# BlinkBoard_micro_v1_JACDAC.net
KiCad netlist of a schematic drawn in Altium Designer
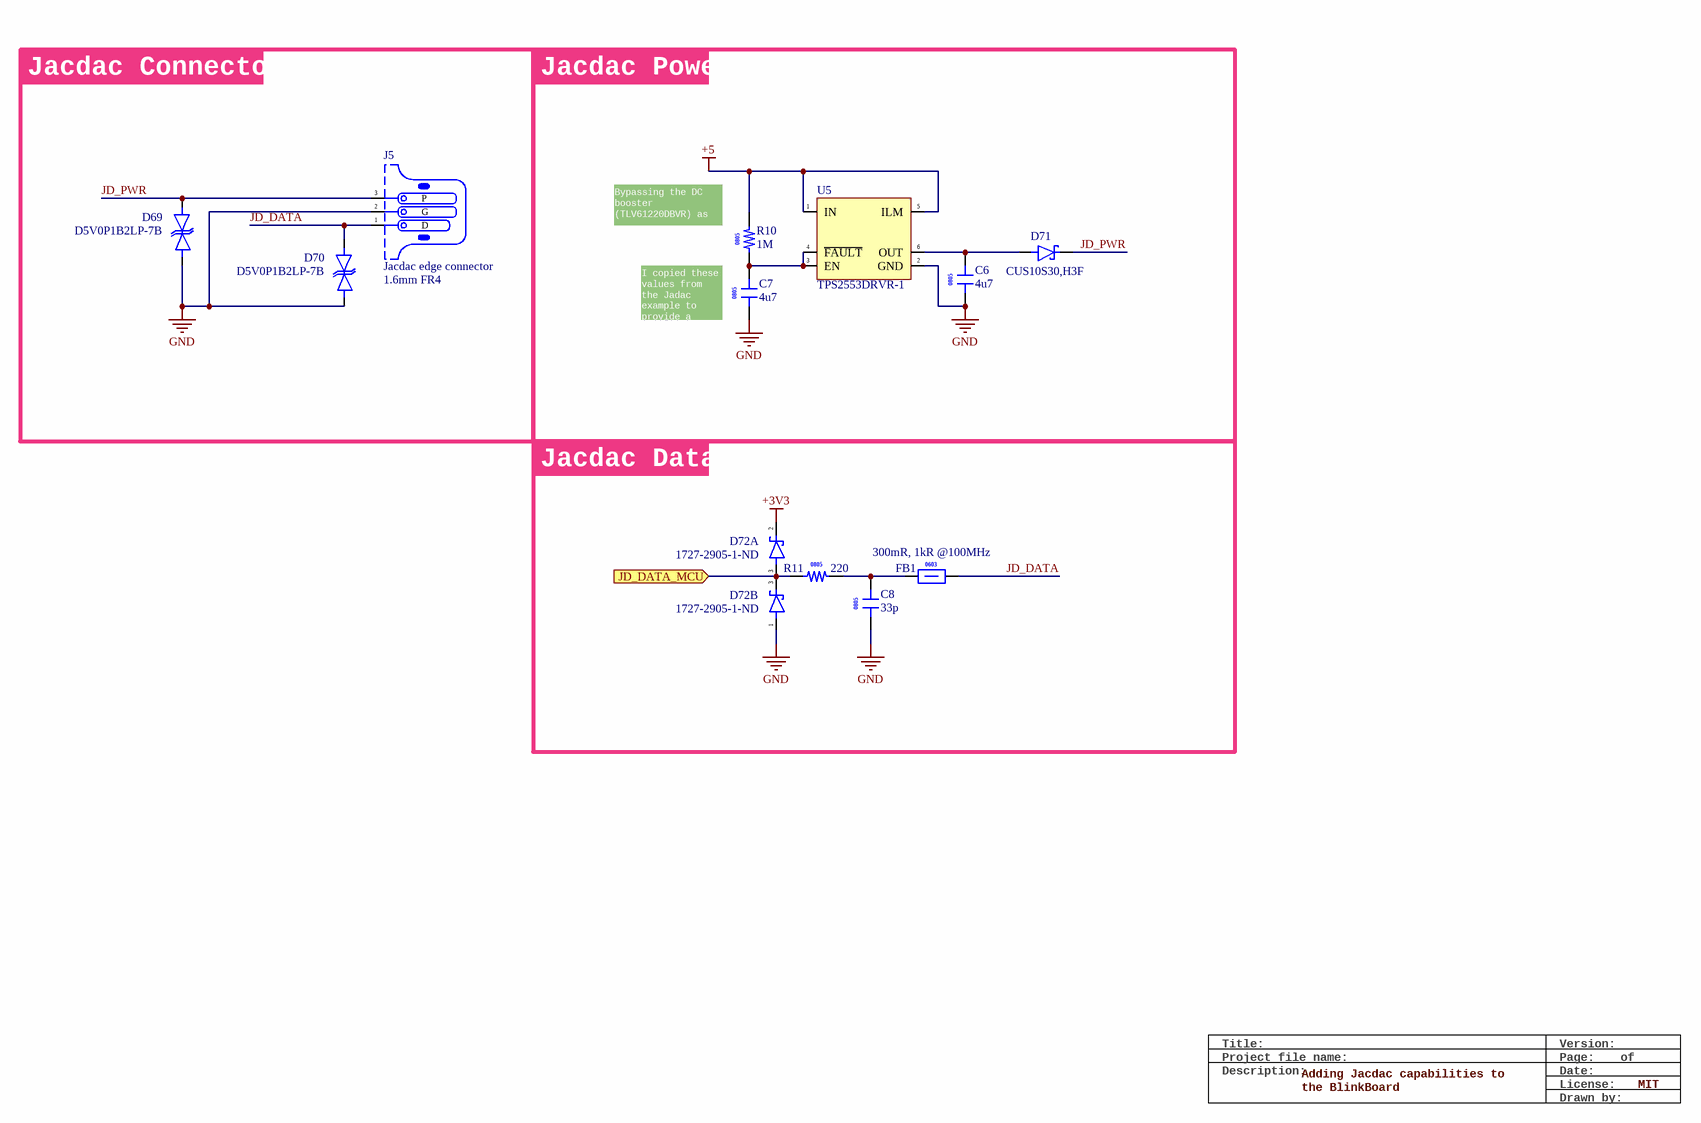
[diagram p0: BlinkBoard_micro_v1_JACDAC.SchDoc]

(export (version "E")
  (design (tool "Eeschema 10.0.6"))
  (components
    (comp (ref "C6")
      (value "4u7")
      (footprint "C0805")
      (description "Multilayer Ceramic Capacitors MLCC - SMD/SMT 4.7uF 6.3V X5R 10%")
      (fields
        (field (name "MANUFACTURER") "Yageo")
        (field (name "MANUFACTURER PART NUMBER") "CC0805KRX5R5BB475")
      )
      (libsource (lib "Passives") (part "C0805_4u7"))
    )
    (comp (ref "C7")
      (value "4u7")
      (footprint "C0805")
      (description "Multilayer Ceramic Capacitors MLCC - SMD/SMT 4.7uF 6.3V X5R 10%")
      (fields
        (field (name "MANUFACTURER") "Yageo")
        (field (name "MANUFACTURER PART NUMBER") "CC0805KRX5R5BB475")
      )
      (libsource (lib "Passives") (part "C0805_4u7"))
    )
    (comp (ref "C8")
      (value "33p")
      (footprint "C0805")
      (description "Cap Ceramic 33pF 50V C0G 5% SMD 0805 125C Paper T/R")
      (fields
        (field (name "MANUFACTURER") "Yageo")
        (field (name "MANUFACTURER PART NUMBER") "CC0805JRNPO9BN330")
      )
      (libsource (lib "Passives") (part "C0805_33p"))
    )
    (comp (ref "D69")
      (value "D5V0P1B2LP-7B")
      (footprint "D5V0P1B2LP")
      (description "TVS DIODE 5.5V 13V DFN1006-2")
      (fields (field (name "MANUFACTURER") "Diodes"))
      (libsource (lib "Diodes") (part "ZENER"))
    )
    (comp (ref "D70")
      (value "D5V0P1B2LP-7B")
      (footprint "D5V0P1B2LP")
      (description "TVS DIODE 5.5V 13V DFN1006-2")
      (fields (field (name "MANUFACTURER") "Diodes"))
      (libsource (lib "Diodes") (part "ZENER"))
    )
    (comp (ref "D71")
      (value "CUS10S30,H3F")
      (footprint "FP-USC-MFG")
      (description "DIODE SCHOTTKY 30V 1A USC")
      (fields (field (name "MANUFACTURER") "Toshiba"))
      (libsource (lib "Diodes") (part "SCHOTTKY_1A"))
    )
    (comp (ref "D72")
      (value "1727-2905-1-ND")
      (footprint "SOT323")
      (description "Rectifier Diode Schottky 0.2A 5ns Automotive 3-Pin SC-70 T/R")
      (fields
        (field (name "MANUFACTURER") "Nexperia")
        (field (name "MANUFACTURER PART NUMBER") "BAT54SW,115")
      )
      (libsource (lib "Diodes") (part "BAT54SW"))
    )
    (comp (ref "FB1")
      (value "300mR, 1kR @100MHz")
      (footprint "BEAD0603")
      (description "Ferrite Beads Multi-Layer Chip Bead 1KOhm 25% 100MHz 600mA 0603 T/R")
      (fields
        (field (name "MANUFACTURER") "Wurth Electronics")
        (field (name "MANUFACTURER PART NUMBER") "742792662")
      )
      (libsource (lib "Passives") (part "BEAD0603"))
    )
    (comp (ref "J5")
      (value "Jacdac edge connector")
      (footprint "Jacdac:JACDAC_EDGE_CONNECTOR_NO_TRACES")
      (description "3 pin Jacdac edge connector 1.27mm pitch")
      (fields
        (field (name "MANUFACTURER PART NUMBER") "JACDAC_EDGE_CONNECTOR")
        (field (name "PCB TYPE") "1.6mm FR4")
        (field (name "CHECKED BY") "S. Hodges")
        (field (name "CREATED BY") "D. Gakure")
      )
      (libsource (lib "Jacdac") (part "Jacdac edge connector"))
    )
    (comp (ref "R10")
      (value "1M")
      (footprint "R0805")
      (description "RES SMD 1M OHM 0.1% 1/8W 0805")
      (fields
        (field (name "MANUFACTURER") "Yageo")
        (field (name "MANUFACTURER PART NUMBER") "RT0805BRE071ML")
      )
      (libsource (lib "Passives") (part "R0805_1M"))
    )
    (comp (ref "R11")
      (value "220")
      (footprint "R0805")
      (description "Res General Purpose Thick Film 0805 220 Ohm 5% 1/8W ±100ppm/°C Molded SMD Paper T/R")
      (fields
        (field (name "MANUFACTURER") "Yageo")
        (field (name "MANUFACTURER PART NUMBER") "RC0805JR-07220RL")
      )
      (libsource (lib "Passives") (part "R0805_220"))
    )
    (comp (ref "U5")
      (value "TPS2553DRVR-1")
      (footprint "DRV0006A_V")
      (description "IC PWR DIST SWITCH ADJ 6SON")
      (fields (field (name "MANUFACTURER") "Texas Instruments"))
      (libsource (lib "IC") (part "TPS2553"))
    )
  )
  (nets
    (net (code "1") (name "+3V3") (class "Default")
      (node (ref "D72") (pin "2") (pinfunction "2_2") (pintype "passive"))
    )
    (net (code "2") (name "+5") (class "Default")
      (node (ref "R10") (pin "2") (pinfunction "2_2") (pintype "passive"))
      (node (ref "U5") (pin "1") (pinfunction "IN_1") (pintype "passive"))
      (node (ref "U5") (pin "5") (pinfunction "ILM_5") (pintype "passive"))
    )
    (net (code "3") (name "/JD_DATA") (class "Default")
      (node (ref "D70") (pin "2") (pinfunction "2_2") (pintype "passive"))
      (node (ref "FB1") (pin "2") (pinfunction "2_2") (pintype "passive"))
      (node (ref "J5") (pin "1") (pinfunction "D_1") (pintype "passive"))
    )
    (net (code "4") (name "/JD_DATA_MCU") (class "Default")
      (node (ref "D72") (pin "3") (pinfunction "3_3") (pintype "passive"))
      (node (ref "R11") (pin "1") (pinfunction "1_1") (pintype "passive"))
    )
    (net (code "5") (name "/JD_PWR") (class "Default")
      (node (ref "D69") (pin "2") (pinfunction "2_2") (pintype "passive"))
      (node (ref "D71") (pin "1") (pinfunction "C_1") (pintype "passive"))
      (node (ref "J5") (pin "3") (pinfunction "P_3") (pintype "passive"))
    )
    (net (code "6") (name "GND") (class "Default")
      (node (ref "C6") (pin "1") (pinfunction "1_1") (pintype "passive"))
      (node (ref "C7") (pin "1") (pinfunction "1_1") (pintype "passive"))
      (node (ref "C8") (pin "1") (pinfunction "1_1") (pintype "passive"))
      (node (ref "D69") (pin "1") (pinfunction "1_1") (pintype "passive"))
      (node (ref "D70") (pin "1") (pinfunction "1_1") (pintype "passive"))
      (node (ref "D72") (pin "1") (pinfunction "1_1") (pintype "passive"))
      (node (ref "J5") (pin "2") (pinfunction "G_2") (pintype "passive"))
      (node (ref "U5") (pin "2") (pinfunction "GND_2") (pintype "passive"))
    )
    (net (code "7") (name "Net-(C8-Pad2)") (class "Default")
      (node (ref "C8") (pin "2") (pinfunction "2_2") (pintype "passive"))
      (node (ref "FB1") (pin "1") (pinfunction "1_1") (pintype "passive"))
      (node (ref "R11") (pin "2") (pinfunction "2_2") (pintype "passive"))
    )
    (net (code "8") (name "Net-(D71-A)") (class "Default")
      (node (ref "C6") (pin "2") (pinfunction "2_2") (pintype "passive"))
      (node (ref "D71") (pin "2") (pinfunction "A_2") (pintype "passive"))
      (node (ref "U5") (pin "6") (pinfunction "OUT_6") (pintype "passive"))
    )
    (net (code "9") (name "Net-(U5-EN)") (class "Default")
      (node (ref "C7") (pin "2") (pinfunction "2_2") (pintype "passive"))
      (node (ref "R10") (pin "1") (pinfunction "1_1") (pintype "passive"))
      (node (ref "U5") (pin "3") (pinfunction "EN_3") (pintype "passive"))
      (node (ref "U5") (pin "4") (pinfunction "~{FAULT}_4") (pintype "passive"))
    )
  )
)
